# ODR_override_rev_1a.net
KiCad netlist of a schematic drawn in EAGLE
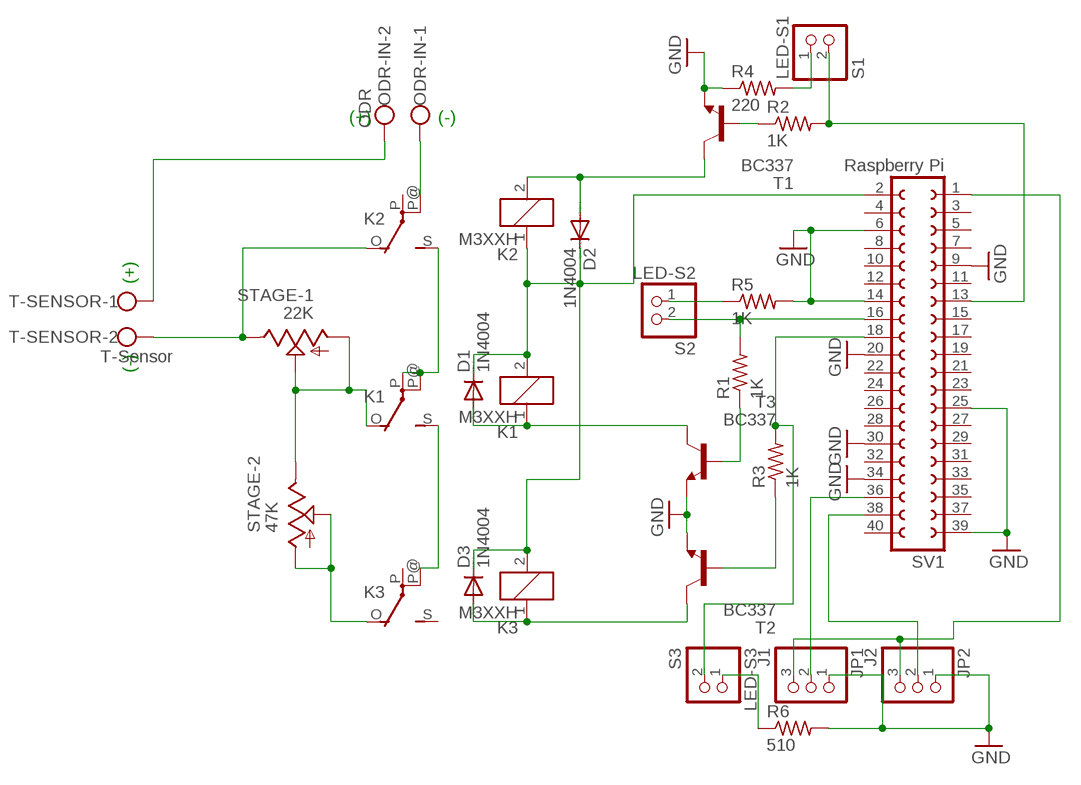
[diagram p0: schematic, sheet 1]

(export (version "E")
  (design (tool "Eeschema 10.0.6"))
  (components
    (comp (ref "D1")
      (value "1N4004")
      (footprint "eagle-import:DO41-10")
      (libsource (lib "eagle-import") (part "1N4004"))
    )
    (comp (ref "D2")
      (value "1N4004")
      (footprint "eagle-import:DO41-10")
      (libsource (lib "eagle-import") (part "1N4004"))
    )
    (comp (ref "D3")
      (value "1N4004")
      (footprint "eagle-import:DO41-10")
      (libsource (lib "eagle-import") (part "1N4004"))
    )
    (comp (ref "JP1")
      (value "J1")
      (footprint "eagle-import:1X03")
      (libsource (lib "eagle-import") (part "PINHD-1X3"))
    )
    (comp (ref "JP2")
      (value "J2")
      (footprint "eagle-import:1X03")
      (libsource (lib "eagle-import") (part "PINHD-1X3"))
    )
    (comp (ref "K1")
      (value "M3XXH")
      (footprint "eagle-import:M3XXH")
      (libsource (lib "eagle-import") (part "M3XXH"))
    )
    (comp (ref "K2")
      (value "M3XXH")
      (footprint "eagle-import:M3XXH")
      (libsource (lib "eagle-import") (part "M3XXH"))
    )
    (comp (ref "K3")
      (value "M3XXH")
      (footprint "eagle-import:M3XXH")
      (libsource (lib "eagle-import") (part "M3XXH"))
    )
    (comp (ref "LED-S1")
      (value "S1")
      (footprint "eagle-import:1X02")
      (libsource (lib "eagle-import") (part "PINHD-1X2"))
    )
    (comp (ref "LED-S2")
      (value "S2")
      (footprint "eagle-import:1X02")
      (libsource (lib "eagle-import") (part "PINHD-1X2"))
    )
    (comp (ref "LED-S3")
      (value "S3")
      (footprint "eagle-import:1X02")
      (libsource (lib "eagle-import") (part "PINHD-1X2"))
    )
    (comp (ref "ODR-IN")
      (value "ODR")
      (footprint "eagle-import:W237-102")
      (fields (field (name "MPN") "237-102"))
      (libsource (lib "eagle-import") (part "W237-102"))
    )
    (comp (ref "R1")
      (value "1K")
      (footprint "eagle-import:0204_7")
      (libsource (lib "eagle-import") (part "R-US_0204/7"))
    )
    (comp (ref "R2")
      (value "1K")
      (footprint "eagle-import:0204_7")
      (libsource (lib "eagle-import") (part "R-US_0204/7"))
    )
    (comp (ref "R3")
      (value "1K")
      (footprint "eagle-import:0204_7")
      (libsource (lib "eagle-import") (part "R-US_0204/7"))
    )
    (comp (ref "R4")
      (value "220")
      (footprint "eagle-import:0204_7")
      (libsource (lib "eagle-import") (part "R-US_0204/7"))
    )
    (comp (ref "R5")
      (value "1K")
      (footprint "eagle-import:0204_7")
      (libsource (lib "eagle-import") (part "R-US_0204/7"))
    )
    (comp (ref "R6")
      (value "510")
      (footprint "eagle-import:0204_7")
      (libsource (lib "eagle-import") (part "R-US_0204/7"))
    )
    (comp (ref "STAGE-1")
      (value "22K")
      (footprint "eagle-import:B25P")
      (libsource (lib "eagle-import") (part "TRIM_US-B25P"))
    )
    (comp (ref "STAGE-2")
      (value "47K")
      (footprint "eagle-import:B25P")
      (libsource (lib "eagle-import") (part "TRIM_US-B25P"))
    )
    (comp (ref "SV1")
      (value "Raspberry Pi")
      (footprint "eagle-import:FE20-2")
      (libsource (lib "eagle-import") (part "FE20-2"))
    )
    (comp (ref "T-SENSOR")
      (value "T-Sensor")
      (footprint "eagle-import:W237-102")
      (fields (field (name "MPN") "237-102"))
      (libsource (lib "eagle-import") (part "W237-102"))
    )
    (comp (ref "T1")
      (value "BC337")
      (footprint "eagle-import:TO92")
      (libsource (lib "eagle-import") (part "BC337"))
    )
    (comp (ref "T2")
      (value "BC337")
      (footprint "eagle-import:TO92")
      (libsource (lib "eagle-import") (part "BC337"))
    )
    (comp (ref "T3")
      (value "BC337")
      (footprint "eagle-import:TO92")
      (libsource (lib "eagle-import") (part "BC337"))
    )
  )
  (nets
    (net (code "1") (name "GND") (class "Default")
      (node (ref "JP1") (pin "1") (pinfunction "1_1") (pintype "passive"))
      (node (ref "JP2") (pin "1") (pinfunction "1_1") (pintype "passive"))
      (node (ref "R4") (pin "1") (pinfunction "1_1") (pintype "passive"))
      (node (ref "R5") (pin "2") (pinfunction "2_2") (pintype "passive"))
      (node (ref "R6") (pin "2") (pinfunction "2_2") (pintype "passive"))
      (node (ref "SV1") (pin "14") (pinfunction "14_14") (pintype "passive"))
      (node (ref "SV1") (pin "20") (pinfunction "20_20") (pintype "passive"))
      (node (ref "SV1") (pin "25") (pinfunction "25_25") (pintype "passive"))
      (node (ref "SV1") (pin "30") (pinfunction "30_30") (pintype "passive"))
      (node (ref "SV1") (pin "34") (pinfunction "34_34") (pintype "passive"))
      (node (ref "SV1") (pin "39") (pinfunction "39_39") (pintype "passive"))
      (node (ref "SV1") (pin "6") (pinfunction "6_6") (pintype "passive"))
      (node (ref "SV1") (pin "9") (pinfunction "9_9") (pintype "passive"))
      (node (ref "T1") (pin "1") (pinfunction "E_1") (pintype "passive"))
      (node (ref "T2") (pin "1") (pinfunction "E_1") (pintype "passive"))
      (node (ref "T3") (pin "1") (pinfunction "E_1") (pintype "passive"))
    )
    (net (code "2") (name "Net-(D1-PadC)") (class "Default")
      (node (ref "D1") (pin "C") (pinfunction "C_C") (pintype "passive"))
      (node (ref "D2") (pin "C") (pinfunction "C_C") (pintype "passive"))
      (node (ref "D3") (pin "C") (pinfunction "C_C") (pintype "passive"))
      (node (ref "K1") (pin "2") (pinfunction "2_2") (pintype "passive"))
      (node (ref "K2") (pin "1") (pinfunction "1_1") (pintype "passive"))
      (node (ref "K3") (pin "2") (pinfunction "2_2") (pintype "passive"))
      (node (ref "SV1") (pin "2") (pinfunction "2_2") (pintype "passive"))
    )
    (net (code "3") (name "Net-(JP1-Pad2)") (class "Default")
      (node (ref "JP1") (pin "2") (pinfunction "2_2") (pintype "passive"))
      (node (ref "SV1") (pin "36") (pinfunction "36_36") (pintype "passive"))
    )
    (net (code "4") (name "Net-(JP1-Pad3)") (class "Default")
      (node (ref "JP1") (pin "3") (pinfunction "3_3") (pintype "passive"))
      (node (ref "JP2") (pin "3") (pinfunction "3_3") (pintype "passive"))
      (node (ref "SV1") (pin "1") (pinfunction "1_1") (pintype "passive"))
    )
    (net (code "5") (name "Net-(JP2-Pad2)") (class "Default")
      (node (ref "JP2") (pin "2") (pinfunction "2_2") (pintype "passive"))
      (node (ref "SV1") (pin "38") (pinfunction "38_38") (pintype "passive"))
    )
    (net (code "6") (name "Net-(K1-PadO)") (class "Default")
      (node (ref "K1") (pin "O") (pinfunction "O_O") (pintype "passive"))
      (node (ref "STAGE-1") (pin "A") (pinfunction "A_A") (pintype "passive"))
      (node (ref "STAGE-1") (pin "S") (pinfunction "S_S") (pintype "passive"))
      (node (ref "STAGE-2") (pin "E") (pinfunction "E_E") (pintype "passive"))
    )
    (net (code "7") (name "Net-(K1-PadP)") (class "Default")
      (node (ref "K1") (pin "P") (pinfunction "P_P") (pintype "passive"))
      (node (ref "K1") (pin "P@") (pinfunction "P_P@") (pintype "passive"))
      (node (ref "K2") (pin "S") (pinfunction "S_S") (pintype "passive"))
    )
    (net (code "8") (name "Net-(K1-PadS)") (class "Default")
      (node (ref "K1") (pin "S") (pinfunction "S_S") (pintype "passive"))
      (node (ref "K3") (pin "P@") (pinfunction "P_P@") (pintype "passive"))
    )
    (net (code "9") (name "Net-(K3-PadO)") (class "Default")
      (node (ref "K3") (pin "O") (pinfunction "O_O") (pintype "passive"))
      (node (ref "STAGE-2") (pin "A") (pinfunction "A_A") (pintype "passive"))
      (node (ref "STAGE-2") (pin "S") (pinfunction "S_S") (pintype "passive"))
    )
    (net (code "10") (name "Net-(LED-S1-Pad1)") (class "Default")
      (node (ref "LED-S1") (pin "1") (pinfunction "1_1") (pintype "passive"))
      (node (ref "R4") (pin "2") (pinfunction "2_2") (pintype "passive"))
    )
    (net (code "11") (name "Net-(LED-S1-Pad2)") (class "Default")
      (node (ref "LED-S1") (pin "2") (pinfunction "2_2") (pintype "passive"))
      (node (ref "R2") (pin "2") (pinfunction "2_2") (pintype "passive"))
      (node (ref "SV1") (pin "13") (pinfunction "13_13") (pintype "passive"))
    )
    (net (code "12") (name "Net-(LED-S2-Pad1)") (class "Default")
      (node (ref "LED-S2") (pin "1") (pinfunction "1_1") (pintype "passive"))
      (node (ref "R5") (pin "1") (pinfunction "1_1") (pintype "passive"))
    )
    (net (code "13") (name "Net-(LED-S2-Pad2)") (class "Default")
      (node (ref "LED-S2") (pin "2") (pinfunction "2_2") (pintype "passive"))
      (node (ref "R1") (pin "2") (pinfunction "2_2") (pintype "passive"))
      (node (ref "SV1") (pin "16") (pinfunction "16_16") (pintype "passive"))
    )
    (net (code "14") (name "Net-(LED-S3-Pad1)") (class "Default")
      (node (ref "LED-S3") (pin "1") (pinfunction "1_1") (pintype "passive"))
      (node (ref "R6") (pin "1") (pinfunction "1_1") (pintype "passive"))
    )
    (net (code "15") (name "Net-(LED-S3-Pad2)") (class "Default")
      (node (ref "LED-S3") (pin "2") (pinfunction "2_2") (pintype "passive"))
      (node (ref "R3") (pin "2") (pinfunction "2_2") (pintype "passive"))
      (node (ref "SV1") (pin "18") (pinfunction "18_18") (pintype "passive"))
    )
    (net (code "16") (name "Net-(ODR-INA-KL)") (class "Default")
      (node (ref "K2") (pin "P@") (pinfunction "P_P@") (pintype "passive"))
      (node (ref "ODR-IN") (pin "1") (pinfunction "KL_1") (pintype "passive"))
    )
    (net (code "17") (name "Net-(ODR-INB-KL)") (class "Default")
      (node (ref "ODR-IN") (pin "2") (pinfunction "KL_2") (pintype "passive"))
      (node (ref "T-SENSOR") (pin "1") (pinfunction "KL_1") (pintype "passive"))
    )
    (net (code "18") (name "Net-(T-SENSORB-KL)") (class "Default")
      (node (ref "K2") (pin "O") (pinfunction "O_O") (pintype "passive"))
      (node (ref "STAGE-1") (pin "E") (pinfunction "E_E") (pintype "passive"))
      (node (ref "T-SENSOR") (pin "2") (pinfunction "KL_2") (pintype "passive"))
    )
    (net (code "19") (name "Net-(T1-B)") (class "Default")
      (node (ref "R2") (pin "1") (pinfunction "1_1") (pintype "passive"))
      (node (ref "T1") (pin "2") (pinfunction "B_2") (pintype "passive"))
    )
    (net (code "20") (name "Net-(T1-C)") (class "Default")
      (node (ref "D2") (pin "A") (pinfunction "A_A") (pintype "passive"))
      (node (ref "K2") (pin "2") (pinfunction "2_2") (pintype "passive"))
      (node (ref "T1") (pin "3") (pinfunction "C_3") (pintype "passive"))
    )
    (net (code "21") (name "Net-(T2-B)") (class "Default")
      (node (ref "R3") (pin "1") (pinfunction "1_1") (pintype "passive"))
      (node (ref "T2") (pin "2") (pinfunction "B_2") (pintype "passive"))
    )
    (net (code "22") (name "Net-(T2-C)") (class "Default")
      (node (ref "D3") (pin "A") (pinfunction "A_A") (pintype "passive"))
      (node (ref "K3") (pin "1") (pinfunction "1_1") (pintype "passive"))
      (node (ref "T2") (pin "3") (pinfunction "C_3") (pintype "passive"))
    )
    (net (code "23") (name "Net-(T3-B)") (class "Default")
      (node (ref "R1") (pin "1") (pinfunction "1_1") (pintype "passive"))
      (node (ref "T3") (pin "2") (pinfunction "B_2") (pintype "passive"))
    )
    (net (code "24") (name "Net-(T3-C)") (class "Default")
      (node (ref "D1") (pin "A") (pinfunction "A_A") (pintype "passive"))
      (node (ref "K1") (pin "1") (pinfunction "1_1") (pintype "passive"))
      (node (ref "T3") (pin "3") (pinfunction "C_3") (pintype "passive"))
    )
    (net (code "25") (name "unconnected-(K2-PadP)") (class "Default")
      (node (ref "K2") (pin "P") (pinfunction "P_P") (pintype "passive"))
    )
    (net (code "26") (name "unconnected-(K3-PadP)") (class "Default")
      (node (ref "K3") (pin "P") (pinfunction "P_P") (pintype "passive"))
    )
    (net (code "27") (name "unconnected-(K3-PadS)") (class "Default")
      (node (ref "K3") (pin "S") (pinfunction "S_S") (pintype "passive"))
    )
    (net (code "28") (name "unconnected-(SV1-Pad3)") (class "Default")
      (node (ref "SV1") (pin "3") (pinfunction "3_3") (pintype "passive"))
    )
    (net (code "29") (name "unconnected-(SV1-Pad4)") (class "Default")
      (node (ref "SV1") (pin "4") (pinfunction "4_4") (pintype "passive"))
    )
    (net (code "30") (name "unconnected-(SV1-Pad5)") (class "Default")
      (node (ref "SV1") (pin "5") (pinfunction "5_5") (pintype "passive"))
    )
    (net (code "31") (name "unconnected-(SV1-Pad7)") (class "Default")
      (node (ref "SV1") (pin "7") (pinfunction "7_7") (pintype "passive"))
    )
    (net (code "32") (name "unconnected-(SV1-Pad8)") (class "Default")
      (node (ref "SV1") (pin "8") (pinfunction "8_8") (pintype "passive"))
    )
    (net (code "33") (name "unconnected-(SV1-Pad10)") (class "Default")
      (node (ref "SV1") (pin "10") (pinfunction "10_10") (pintype "passive"))
    )
    (net (code "34") (name "unconnected-(SV1-Pad11)") (class "Default")
      (node (ref "SV1") (pin "11") (pinfunction "11_11") (pintype "passive"))
    )
    (net (code "35") (name "unconnected-(SV1-Pad12)") (class "Default")
      (node (ref "SV1") (pin "12") (pinfunction "12_12") (pintype "passive"))
    )
    (net (code "36") (name "unconnected-(SV1-Pad15)") (class "Default")
      (node (ref "SV1") (pin "15") (pinfunction "15_15") (pintype "passive"))
    )
    (net (code "37") (name "unconnected-(SV1-Pad17)") (class "Default")
      (node (ref "SV1") (pin "17") (pinfunction "17_17") (pintype "passive"))
    )
    (net (code "38") (name "unconnected-(SV1-Pad19)") (class "Default")
      (node (ref "SV1") (pin "19") (pinfunction "19_19") (pintype "passive"))
    )
    (net (code "39") (name "unconnected-(SV1-Pad21)") (class "Default")
      (node (ref "SV1") (pin "21") (pinfunction "21_21") (pintype "passive"))
    )
    (net (code "40") (name "unconnected-(SV1-Pad22)") (class "Default")
      (node (ref "SV1") (pin "22") (pinfunction "22_22") (pintype "passive"))
    )
    (net (code "41") (name "unconnected-(SV1-Pad23)") (class "Default")
      (node (ref "SV1") (pin "23") (pinfunction "23_23") (pintype "passive"))
    )
    (net (code "42") (name "unconnected-(SV1-Pad24)") (class "Default")
      (node (ref "SV1") (pin "24") (pinfunction "24_24") (pintype "passive"))
    )
    (net (code "43") (name "unconnected-(SV1-Pad26)") (class "Default")
      (node (ref "SV1") (pin "26") (pinfunction "26_26") (pintype "passive"))
    )
    (net (code "44") (name "unconnected-(SV1-Pad27)") (class "Default")
      (node (ref "SV1") (pin "27") (pinfunction "27_27") (pintype "passive"))
    )
    (net (code "45") (name "unconnected-(SV1-Pad28)") (class "Default")
      (node (ref "SV1") (pin "28") (pinfunction "28_28") (pintype "passive"))
    )
    (net (code "46") (name "unconnected-(SV1-Pad29)") (class "Default")
      (node (ref "SV1") (pin "29") (pinfunction "29_29") (pintype "passive"))
    )
    (net (code "47") (name "unconnected-(SV1-Pad31)") (class "Default")
      (node (ref "SV1") (pin "31") (pinfunction "31_31") (pintype "passive"))
    )
    (net (code "48") (name "unconnected-(SV1-Pad32)") (class "Default")
      (node (ref "SV1") (pin "32") (pinfunction "32_32") (pintype "passive"))
    )
    (net (code "49") (name "unconnected-(SV1-Pad33)") (class "Default")
      (node (ref "SV1") (pin "33") (pinfunction "33_33") (pintype "passive"))
    )
    (net (code "50") (name "unconnected-(SV1-Pad35)") (class "Default")
      (node (ref "SV1") (pin "35") (pinfunction "35_35") (pintype "passive"))
    )
    (net (code "51") (name "unconnected-(SV1-Pad37)") (class "Default")
      (node (ref "SV1") (pin "37") (pinfunction "37_37") (pintype "passive"))
    )
    (net (code "52") (name "unconnected-(SV1-Pad40)") (class "Default")
      (node (ref "SV1") (pin "40") (pinfunction "40_40") (pintype "passive"))
    )
  )
)
